# main_board_v2_3.net
KiCad netlist of a schematic drawn in EAGLE
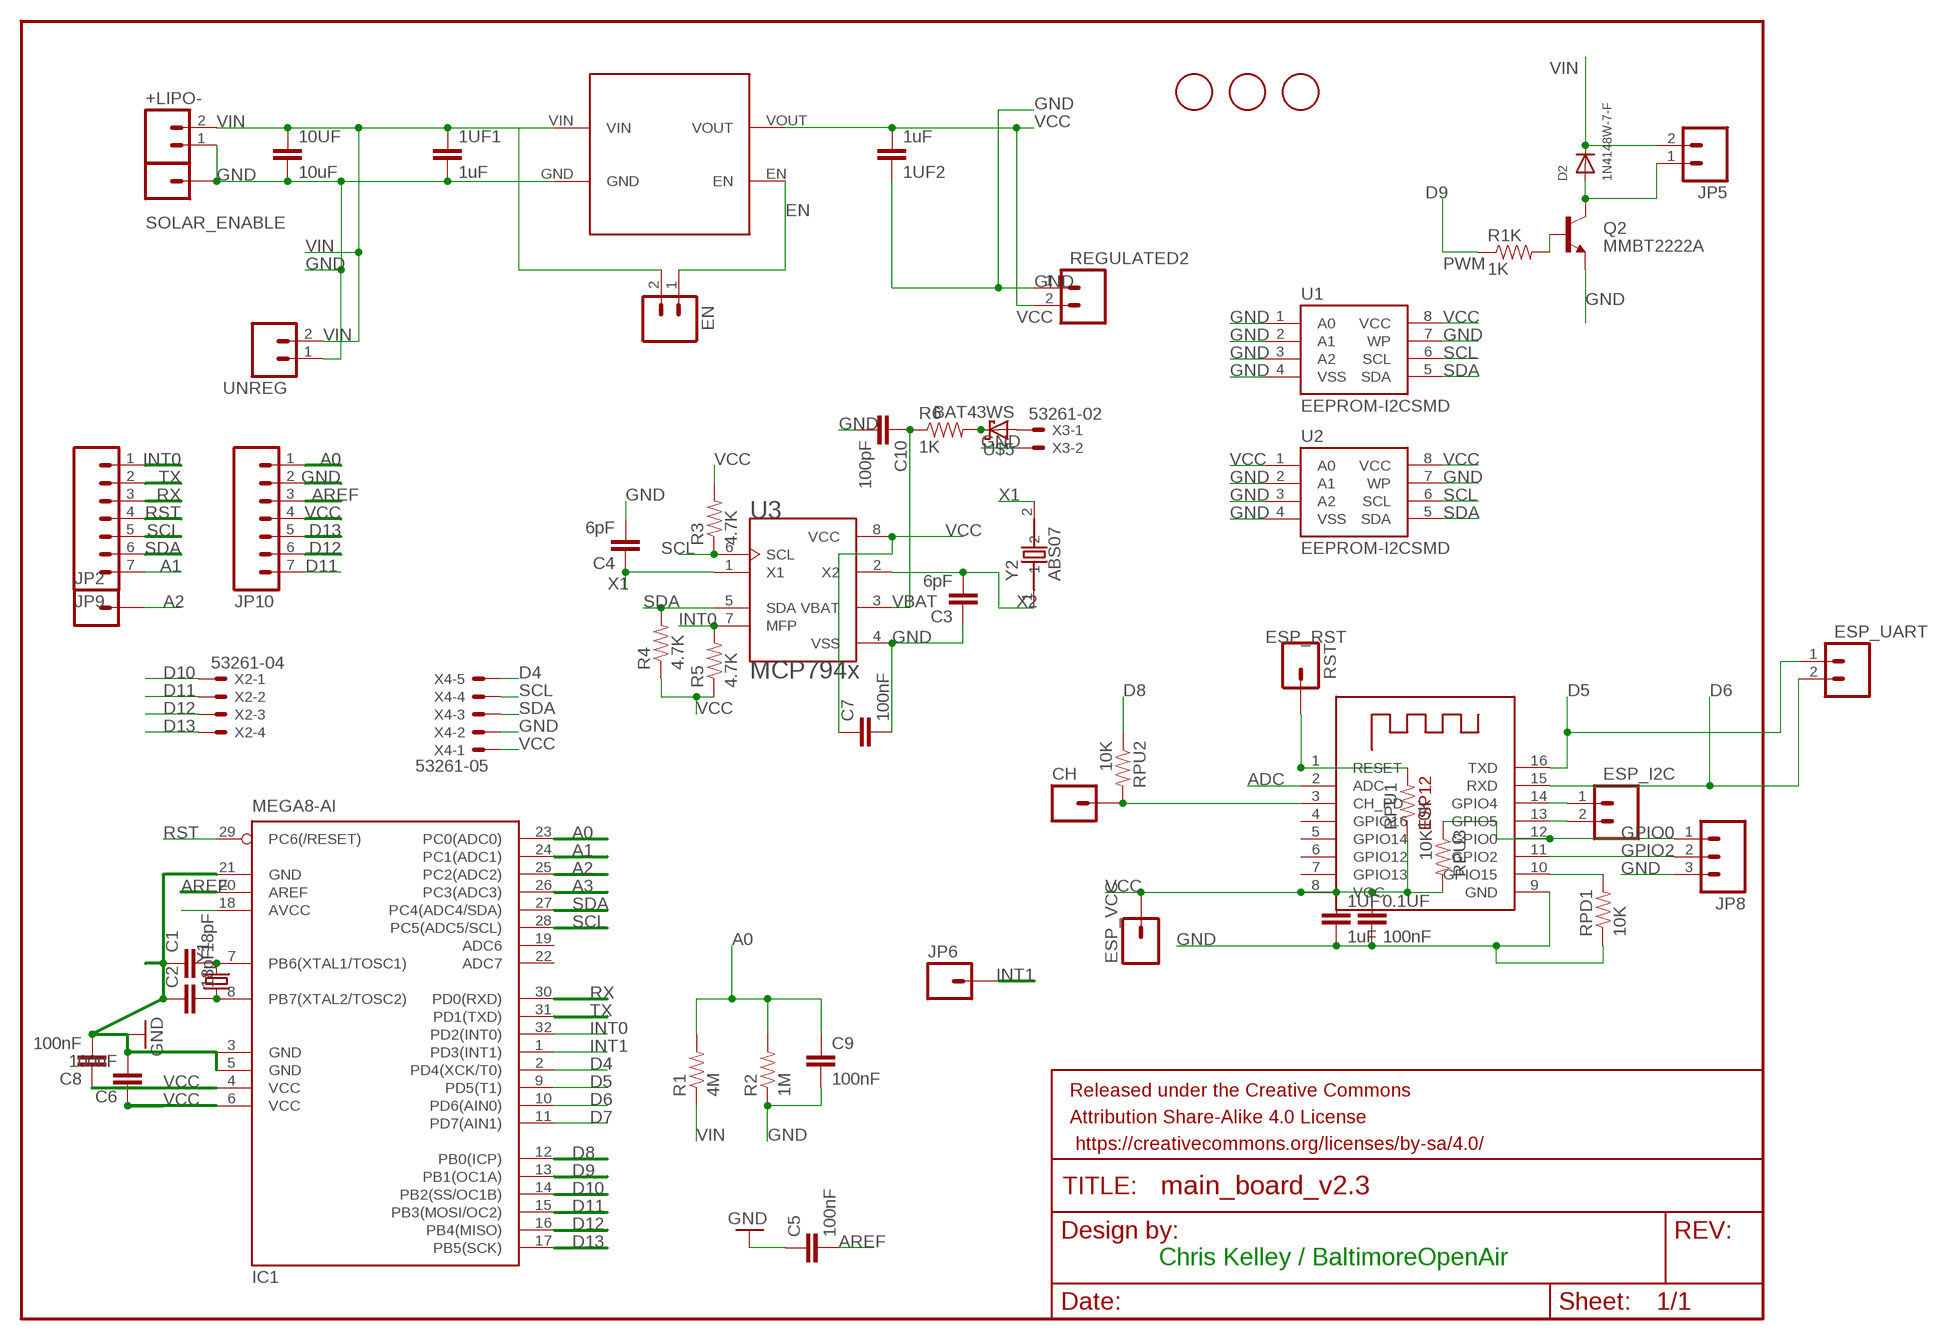
[diagram p0: schematic, sheet 1]

(export (version "E")
  (design (tool "Eeschema 10.0.6"))
  (components
    (comp (ref "+LIPO-")
      (value "M02PTH")
      (footprint "eagle-import:1X02")
      (libsource (lib "eagle-import") (part "M02PTH"))
    )
    (comp (ref "0.1UF")
      (value "100nF")
      (footprint "eagle-import:0603-CAP")
      (libsource (lib "eagle-import") (part "SparkFun-Passives_CAP0603-CAP"))
    )
    (comp (ref "1UF")
      (value "1uF")
      (footprint "eagle-import:0603-CAP")
      (libsource (lib "eagle-import") (part "SparkFun-Passives_CAP0603-CAP"))
    )
    (comp (ref "1UF1")
      (value "1uF")
      (footprint "eagle-import:0603-CAP")
      (libsource (lib "eagle-import") (part "SparkFun-Passives_CAP0603-CAP"))
    )
    (comp (ref "1UF2")
      (value "1uF")
      (footprint "eagle-import:0603-CAP")
      (libsource (lib "eagle-import") (part "SparkFun-Passives_CAP0603-CAP"))
    )
    (comp (ref "10UF")
      (value "10uF")
      (footprint "eagle-import:0805")
      (libsource (lib "eagle-import") (part "SparkFun-Passives_CAP0805"))
    )
    (comp (ref "C1")
      (value "18pF")
      (footprint "eagle-import:0603-CAP")
      (libsource (lib "eagle-import") (part "CAP0603-CAP"))
    )
    (comp (ref "C2")
      (value "18pF")
      (footprint "eagle-import:0603-CAP")
      (libsource (lib "eagle-import") (part "CAP0603-CAP"))
    )
    (comp (ref "C3")
      (value "6pF")
      (footprint "eagle-import:0603-CAP")
      (libsource (lib "eagle-import") (part "SparkFun-Passives_CAP0603-CAP"))
    )
    (comp (ref "C4")
      (value "6pF")
      (footprint "eagle-import:0603-CAP")
      (libsource (lib "eagle-import") (part "SparkFun-Passives_CAP0603-CAP"))
    )
    (comp (ref "C5")
      (value "100nF")
      (footprint "eagle-import:0603-CAP")
      (libsource (lib "eagle-import") (part "CAP0603-CAP"))
    )
    (comp (ref "C6")
      (value "100nF")
      (footprint "eagle-import:0603-CAP")
      (libsource (lib "eagle-import") (part "CAP0603-CAP"))
    )
    (comp (ref "C7")
      (value "100nF")
      (footprint "eagle-import:0603-CAP")
      (libsource (lib "eagle-import") (part "SparkFun-Passives_CAP0603-CAP"))
    )
    (comp (ref "C8")
      (value "100nF")
      (footprint "eagle-import:0603-CAP")
      (libsource (lib "eagle-import") (part "CAP0603-CAP"))
    )
    (comp (ref "C9")
      (value "100nF")
      (footprint "eagle-import:0603-CAP")
      (libsource (lib "eagle-import") (part "SparkFun-Passives_CAP0603-CAP"))
    )
    (comp (ref "C10")
      (value "100pF")
      (footprint "eagle-import:0603-CAP")
      (libsource (lib "eagle-import") (part "SparkFun-Passives_CAP0603-CAP"))
    )
    (comp (ref "CH")
      (value "M01PTH")
      (footprint "eagle-import:1X01")
      (libsource (lib "eagle-import") (part "M01PTH"))
    )
    (comp (ref "D2")
      (value "1N4148W-7-F")
      (footprint "eagle-import:SOD-123")
      (libsource (lib "eagle-import") (part "DIODESOD-123"))
    )
    (comp (ref "EN")
      (value "M02PTH")
      (footprint "eagle-import:1X02")
      (libsource (lib "eagle-import") (part "M02PTH"))
    )
    (comp (ref "ESP_I2C")
      (value "M02PTH")
      (footprint "eagle-import:1X02")
      (libsource (lib "eagle-import") (part "M02PTH"))
    )
    (comp (ref "ESP_UART")
      (value "M02PTH")
      (footprint "eagle-import:1X02")
      (libsource (lib "eagle-import") (part "M02PTH"))
    )
    (comp (ref "ESP_VCC")
      (value "M01PTH")
      (footprint "eagle-import:1X01")
      (libsource (lib "eagle-import") (part "M01PTH"))
    )
    (comp (ref "FRAME1")
      (value "FRAME-LETTER")
      (footprint "eagle-import:CREATIVE_COMMONS")
      (libsource (lib "eagle-import") (part "FRAME-LETTER"))
    )
    (comp (ref "IC1")
      (value "MEGA8-AI")
      (footprint "eagle-import:TQFP32-08")
      (fields (field (name "MPN") "ATMEGA8-16AU"))
      (libsource (lib "eagle-import") (part "MEGA8-AI"))
    )
    (comp (ref "JP2")
      (value "M01PTH")
      (footprint "eagle-import:1X01")
      (libsource (lib "eagle-import") (part "M01PTH"))
    )
    (comp (ref "JP5")
      (value "M02-JST-2MM-SMT")
      (footprint "eagle-import:JST-2-SMD")
      (libsource (lib "eagle-import") (part "M02-JST-2MM-SMT"))
    )
    (comp (ref "JP6")
      (value "M01PTH")
      (footprint "eagle-import:1X01")
      (libsource (lib "eagle-import") (part "M01PTH"))
    )
    (comp (ref "JP8")
      (value "M03PTH")
      (footprint "eagle-import:1X03")
      (libsource (lib "eagle-import") (part "M03PTH"))
    )
    (comp (ref "JP9")
      (value "M07")
      (footprint "eagle-import:1X07")
      (libsource (lib "eagle-import") (part "M07"))
    )
    (comp (ref "JP10")
      (value "M07")
      (footprint "eagle-import:1X07")
      (libsource (lib "eagle-import") (part "M07"))
    )
    (comp (ref "Q2")
      (value "MMBT2222A")
      (footprint "eagle-import:SOT23-3")
      (libsource (lib "eagle-import") (part "TRANSISTOR_NPNMMBT2222A"))
    )
    (comp (ref "R1")
      (value "4M")
      (footprint "eagle-import:0603-RES")
      (libsource (lib "eagle-import") (part "RESISTOR0603"))
    )
    (comp (ref "R1K")
      (value "1K")
      (footprint "eagle-import:0603-RES")
      (libsource (lib "eagle-import") (part "RESISTOR0603-RES"))
    )
    (comp (ref "R2")
      (value "1M")
      (footprint "eagle-import:0603-RES")
      (libsource (lib "eagle-import") (part "RESISTOR0603"))
    )
    (comp (ref "R3")
      (value "4.7K")
      (footprint "eagle-import:0603-RES")
      (libsource (lib "eagle-import") (part "RESISTOR0603-RES"))
    )
    (comp (ref "R4")
      (value "4.7K")
      (footprint "eagle-import:0603-RES")
      (libsource (lib "eagle-import") (part "RESISTOR0603-RES"))
    )
    (comp (ref "R5")
      (value "4.7K")
      (footprint "eagle-import:0603-RES")
      (libsource (lib "eagle-import") (part "RESISTOR0603-RES"))
    )
    (comp (ref "R6")
      (value "1K")
      (footprint "eagle-import:0603-RES")
      (libsource (lib "eagle-import") (part "RESISTOR0603-RES"))
    )
    (comp (ref "REGULATED2")
      (value "M02PTH")
      (footprint "eagle-import:1X02")
      (libsource (lib "eagle-import") (part "M02PTH"))
    )
    (comp (ref "RPD1")
      (value "10K")
      (footprint "eagle-import:0603-RES")
      (libsource (lib "eagle-import") (part "RESISTOR0603-RES"))
    )
    (comp (ref "RPU1")
      (value "10K")
      (footprint "eagle-import:0603-RES")
      (libsource (lib "eagle-import") (part "RESISTOR0603-RES"))
    )
    (comp (ref "RPU2")
      (value "10K")
      (footprint "eagle-import:0603-RES")
      (libsource (lib "eagle-import") (part "RESISTOR0603-RES"))
    )
    (comp (ref "RPU3")
      (value "10K")
      (footprint "eagle-import:0603-RES")
      (libsource (lib "eagle-import") (part "RESISTOR0603-RES"))
    )
    (comp (ref "RST")
      (value "M01PTH")
      (footprint "eagle-import:1X01")
      (libsource (lib "eagle-import") (part "M01PTH"))
    )
    (comp (ref "SOLAR_ENABLE")
      (value "M01PTH")
      (footprint "eagle-import:1X01")
      (libsource (lib "eagle-import") (part "M01PTH"))
    )
    (comp (ref "U$3")
      (value "FIDUCIAL")
      (footprint "eagle-import:FIDUCIAL_1MM")
      (libsource (lib "eagle-import") (part "FIDUCIAL"))
    )
    (comp (ref "U$4")
      (value "AP2112K")
      (footprint "eagle-import:AP2112K-SOT23-5")
      (libsource (lib "eagle-import") (part "AP2112K"))
    )
    (comp (ref "U$5")
      (value "BAT43WS")
      (footprint "eagle-import:BAT43WS")
      (libsource (lib "eagle-import") (part "BAT43WS"))
    )
    (comp (ref "U$6")
      (value "FIDUCIAL")
      (footprint "eagle-import:FIDUCIAL_1MM")
      (libsource (lib "eagle-import") (part "FIDUCIAL"))
    )
    (comp (ref "U$7")
      (value "FIDUCIAL")
      (footprint "eagle-import:FIDUCIAL_1MM")
      (libsource (lib "eagle-import") (part "FIDUCIAL"))
    )
    (comp (ref "U1")
      (value "EEPROM-I2CSMD")
      (footprint "eagle-import:SO08")
      (libsource (lib "eagle-import") (part "EEPROM-I2CSMD"))
    )
    (comp (ref "U2")
      (value "EEPROM-I2CSMD")
      (footprint "eagle-import:SO08")
      (libsource (lib "eagle-import") (part "EEPROM-I2CSMD"))
    )
    (comp (ref "U3")
      (value "MCP794x")
      (footprint "eagle-import:SOIC127P600X175-8N")
      (fields (field (name "MF") "Microchip") (field (name "MP") "MCP7940M-I/SN"))
      (libsource (lib "eagle-import") (part "MCP7940M-I/SN"))
    )
    (comp (ref "UNREG")
      (value "M02PTH")
      (footprint "eagle-import:1X02")
      (libsource (lib "eagle-import") (part "M02PTH"))
    )
    (comp (ref "X1")
      (value "ESP-12")
      (footprint "eagle-import:ESP-12")
      (libsource (lib "eagle-import") (part "ESP-12"))
    )
    (comp (ref "X2")
      (value "53261-04")
      (footprint "eagle-import:53261-04")
      (libsource (lib "eagle-import") (part "53?-04261"))
    )
    (comp (ref "X3")
      (value "53261-02")
      (footprint "eagle-import:53261-02")
      (libsource (lib "eagle-import") (part "53?-02261"))
    )
    (comp (ref "X4")
      (value "53261-05")
      (footprint "eagle-import:53261-05")
      (libsource (lib "eagle-import") (part "53?-05261"))
    )
    (comp (ref "Y1")
      (value "CRYSTAL5X3")
      (footprint "eagle-import:CRYSTAL-SMD-5X3")
      (libsource (lib "eagle-import") (part "CRYSTAL5X3"))
    )
    (comp (ref "Y2")
      (value "ABS07")
      (footprint "eagle-import:XTAL320X150X90")
      (fields (field (name "MF") "Abracon") (field (name "MP") "ABS07-32.768KHZ-T"))
      (libsource (lib "eagle-import") (part "ABS07-32.768KHZ-T"))
    )
  )
  (nets
    (net (code "1") (name "/A0") (class "Default")
      (node (ref "C9") (pin "1") (pinfunction "1_1") (pintype "passive"))
      (node (ref "IC1") (pin "23") (pinfunction "PC0(ADC0)_23") (pintype "bidirectional"))
      (node (ref "JP10") (pin "1") (pinfunction "1_1") (pintype "passive"))
      (node (ref "R1") (pin "2") (pinfunction "2_2") (pintype "passive"))
      (node (ref "R2") (pin "2") (pinfunction "2_2") (pintype "passive"))
    )
    (net (code "2") (name "/A1") (class "Default")
      (node (ref "IC1") (pin "24") (pinfunction "PC1(ADC1)_24") (pintype "bidirectional"))
      (node (ref "JP9") (pin "7") (pinfunction "7_7") (pintype "passive"))
    )
    (net (code "3") (name "/A2") (class "Default")
      (node (ref "IC1") (pin "25") (pinfunction "PC2(ADC2)_25") (pintype "bidirectional"))
      (node (ref "JP2") (pin "1") (pinfunction "1_1") (pintype "passive"))
    )
    (net (code "4") (name "/A3") (class "Default")
      (node (ref "IC1") (pin "26") (pinfunction "PC3(ADC3)_26") (pintype "bidirectional"))
    )
    (net (code "5") (name "/ADC") (class "Default")
      (node (ref "X1") (pin "2") (pinfunction "ADC_2") (pintype "passive"))
    )
    (net (code "6") (name "/AREF") (class "Default")
      (node (ref "C5") (pin "2") (pinfunction "2_2") (pintype "passive"))
      (node (ref "IC1") (pin "20") (pinfunction "AREF_20") (pintype "passive"))
      (node (ref "JP10") (pin "3") (pinfunction "3_3") (pintype "passive"))
    )
    (net (code "7") (name "/D4") (class "Default")
      (node (ref "IC1") (pin "2") (pinfunction "PD4(XCK/T0)_2") (pintype "bidirectional"))
      (node (ref "X4") (pin "5") (pinfunction "S_5") (pintype "passive"))
    )
    (net (code "8") (name "/D5") (class "Default")
      (node (ref "ESP_UART") (pin "1") (pinfunction "1_1") (pintype "passive"))
      (node (ref "IC1") (pin "9") (pinfunction "PD5(T1)_9") (pintype "bidirectional"))
      (node (ref "X1") (pin "16") (pinfunction "TXD_16") (pintype "output"))
    )
    (net (code "9") (name "/D6") (class "Default")
      (node (ref "ESP_UART") (pin "2") (pinfunction "2_2") (pintype "passive"))
      (node (ref "IC1") (pin "10") (pinfunction "PD6(AIN0)_10") (pintype "bidirectional"))
      (node (ref "X1") (pin "15") (pinfunction "RXD_15") (pintype "input"))
    )
    (net (code "10") (name "/D7") (class "Default")
      (node (ref "IC1") (pin "11") (pinfunction "PD7(AIN1)_11") (pintype "bidirectional"))
    )
    (net (code "11") (name "/D8") (class "Default")
      (node (ref "IC1") (pin "12") (pinfunction "PB0(ICP)_12") (pintype "bidirectional"))
      (node (ref "RPU2") (pin "1") (pinfunction "1_1") (pintype "passive"))
    )
    (net (code "12") (name "/D9") (class "Default")
      (node (ref "IC1") (pin "13") (pinfunction "PB1(OC1A)_13") (pintype "bidirectional"))
      (node (ref "R1K") (pin "1") (pinfunction "1_1") (pintype "passive"))
    )
    (net (code "13") (name "/D10") (class "Default")
      (node (ref "IC1") (pin "14") (pinfunction "PB2(SS/OC1B)_14") (pintype "bidirectional"))
      (node (ref "X2") (pin "1") (pinfunction "S_1") (pintype "passive"))
    )
    (net (code "14") (name "/D11") (class "Default")
      (node (ref "IC1") (pin "15") (pinfunction "PB3(MOSI/OC2)_15") (pintype "bidirectional"))
      (node (ref "JP10") (pin "7") (pinfunction "7_7") (pintype "passive"))
      (node (ref "X2") (pin "2") (pinfunction "S_2") (pintype "passive"))
    )
    (net (code "15") (name "/D12") (class "Default")
      (node (ref "IC1") (pin "16") (pinfunction "PB4(MISO)_16") (pintype "bidirectional"))
      (node (ref "JP10") (pin "6") (pinfunction "6_6") (pintype "passive"))
      (node (ref "X2") (pin "3") (pinfunction "S_3") (pintype "passive"))
    )
    (net (code "16") (name "/D13") (class "Default")
      (node (ref "IC1") (pin "17") (pinfunction "PB5(SCK)_17") (pintype "bidirectional"))
      (node (ref "JP10") (pin "5") (pinfunction "5_5") (pintype "passive"))
      (node (ref "X2") (pin "4") (pinfunction "S_4") (pintype "passive"))
    )
    (net (code "17") (name "/EN") (class "Default")
      (node (ref "EN") (pin "1") (pinfunction "1_1") (pintype "passive"))
      (node (ref "U$4") (pin "EN") (pinfunction "EN_EN") (pintype "bidirectional"))
    )
    (net (code "18") (name "/ESP_RST") (class "Default")
      (node (ref "RPU1") (pin "2") (pinfunction "2_2") (pintype "passive"))
      (node (ref "RST") (pin "1") (pinfunction "1_1") (pintype "passive"))
      (node (ref "X1") (pin "1") (pinfunction "RESET_1") (pintype "input"))
    )
    (net (code "19") (name "/GPIO0") (class "Default")
      (node (ref "JP8") (pin "1") (pinfunction "1_1") (pintype "passive"))
      (node (ref "RPU3") (pin "1") (pinfunction "1_1") (pintype "passive"))
      (node (ref "X1") (pin "12") (pinfunction "GPIO0_12") (pintype "bidirectional"))
    )
    (net (code "20") (name "/GPIO2") (class "Default")
      (node (ref "JP8") (pin "2") (pinfunction "2_2") (pintype "passive"))
      (node (ref "X1") (pin "11") (pinfunction "GPIO2_11") (pintype "bidirectional"))
    )
    (net (code "21") (name "/INT0") (class "Default")
      (node (ref "IC1") (pin "32") (pinfunction "PD2(INT0)_32") (pintype "bidirectional"))
      (node (ref "JP9") (pin "1") (pinfunction "1_1") (pintype "passive"))
      (node (ref "R5") (pin "2") (pinfunction "2_2") (pintype "passive"))
      (node (ref "U3") (pin "7") (pinfunction "MFP_7") (pintype "bidirectional"))
    )
    (net (code "22") (name "/INT1") (class "Default")
      (node (ref "IC1") (pin "1") (pinfunction "PD3(INT1)_1") (pintype "bidirectional"))
      (node (ref "JP6") (pin "1") (pinfunction "1_1") (pintype "passive"))
    )
    (net (code "23") (name "/PWM") (class "Default")
      (node (ref "Q2") (pin "1") (pinfunction "B_1") (pintype "passive"))
      (node (ref "R1K") (pin "2") (pinfunction "2_2") (pintype "passive"))
    )
    (net (code "24") (name "/RST") (class "Default")
      (node (ref "IC1") (pin "29") (pinfunction "PC6(/RESET)_29") (pintype "bidirectional"))
      (node (ref "JP9") (pin "4") (pinfunction "4_4") (pintype "passive"))
    )
    (net (code "25") (name "/RX") (class "Default")
      (node (ref "IC1") (pin "30") (pinfunction "PD0(RXD)_30") (pintype "bidirectional"))
      (node (ref "JP9") (pin "3") (pinfunction "3_3") (pintype "passive"))
    )
    (net (code "26") (name "/SCL") (class "Default")
      (node (ref "IC1") (pin "28") (pinfunction "PC5(ADC5/SCL)_28") (pintype "bidirectional"))
      (node (ref "JP9") (pin "5") (pinfunction "5_5") (pintype "passive"))
      (node (ref "R3") (pin "1") (pinfunction "1_1") (pintype "passive"))
      (node (ref "U1") (pin "6") (pinfunction "SCL_6") (pintype "bidirectional"))
      (node (ref "U2") (pin "6") (pinfunction "SCL_6") (pintype "bidirectional"))
      (node (ref "U3") (pin "6") (pinfunction "SCL_6") (pintype "input"))
      (node (ref "X4") (pin "4") (pinfunction "S_4") (pintype "passive"))
    )
    (net (code "27") (name "/SDA") (class "Default")
      (node (ref "IC1") (pin "27") (pinfunction "PC4(ADC4/SDA)_27") (pintype "bidirectional"))
      (node (ref "JP9") (pin "6") (pinfunction "6_6") (pintype "passive"))
      (node (ref "R4") (pin "2") (pinfunction "2_2") (pintype "passive"))
      (node (ref "U1") (pin "5") (pinfunction "SDA_5") (pintype "bidirectional"))
      (node (ref "U2") (pin "5") (pinfunction "SDA_5") (pintype "bidirectional"))
      (node (ref "U3") (pin "5") (pinfunction "SDA_5") (pintype "bidirectional"))
      (node (ref "X4") (pin "3") (pinfunction "S_3") (pintype "passive"))
    )
    (net (code "28") (name "/TX") (class "Default")
      (node (ref "IC1") (pin "31") (pinfunction "PD1(TXD)_31") (pintype "bidirectional"))
      (node (ref "JP9") (pin "2") (pinfunction "2_2") (pintype "passive"))
    )
    (net (code "29") (name "/VBAT") (class "Default")
      (node (ref "C10") (pin "1") (pinfunction "1_1") (pintype "passive"))
      (node (ref "R6") (pin "1") (pinfunction "1_1") (pintype "passive"))
      (node (ref "U3") (pin "3") (pinfunction "VBAT_3") (pintype "power_in"))
    )
    (net (code "30") (name "/VCC") (class "Default")
      (node (ref "0.1UF") (pin "1") (pinfunction "1_1") (pintype "passive"))
      (node (ref "1UF") (pin "1") (pinfunction "1_1") (pintype "passive"))
      (node (ref "1UF2") (pin "2") (pinfunction "2_2") (pintype "passive"))
      (node (ref "C6") (pin "1") (pinfunction "1_1") (pintype "passive"))
      (node (ref "C7") (pin "1") (pinfunction "1_1") (pintype "passive"))
      (node (ref "C8") (pin "1") (pinfunction "1_1") (pintype "passive"))
      (node (ref "ESP_VCC") (pin "1") (pinfunction "1_1") (pintype "passive"))
      (node (ref "IC1") (pin "18") (pinfunction "AVCC_18") (pintype "power_in"))
      (node (ref "IC1") (pin "4") (pinfunction "VCC_4") (pintype "power_in"))
      (node (ref "IC1") (pin "6") (pinfunction "VCC_6") (pintype "power_in"))
      (node (ref "JP10") (pin "4") (pinfunction "4_4") (pintype "passive"))
      (node (ref "R3") (pin "2") (pinfunction "2_2") (pintype "passive"))
      (node (ref "R4") (pin "1") (pinfunction "1_1") (pintype "passive"))
      (node (ref "R5") (pin "1") (pinfunction "1_1") (pintype "passive"))
      (node (ref "REGULATED2") (pin "2") (pinfunction "2_2") (pintype "passive"))
      (node (ref "RPU1") (pin "1") (pinfunction "1_1") (pintype "passive"))
      (node (ref "RPU3") (pin "2") (pinfunction "2_2") (pintype "passive"))
      (node (ref "U$4") (pin "VOUT") (pinfunction "VOUT_VOUT") (pintype "bidirectional"))
      (node (ref "U1") (pin "8") (pinfunction "VCC_8") (pintype "power_in"))
      (node (ref "U2") (pin "1") (pinfunction "A0_1") (pintype "bidirectional"))
      (node (ref "U2") (pin "8") (pinfunction "VCC_8") (pintype "power_in"))
      (node (ref "U3") (pin "8") (pinfunction "VCC_8") (pintype "power_in"))
      (node (ref "X1") (pin "8") (pinfunction "VCC_8") (pintype "power_in"))
      (node (ref "X4") (pin "1") (pinfunction "S_1") (pintype "passive"))
    )
    (net (code "31") (name "/VIN") (class "Default")
      (node (ref "+LIPO-") (pin "2") (pinfunction "2_2") (pintype "passive"))
      (node (ref "10UF") (pin "1") (pinfunction "1_1") (pintype "passive"))
      (node (ref "1UF1") (pin "1") (pinfunction "1_1") (pintype "passive"))
      (node (ref "D2") (pin "C") (pinfunction "C_C") (pintype "passive"))
      (node (ref "EN") (pin "2") (pinfunction "2_2") (pintype "passive"))
      (node (ref "JP5") (pin "2") (pinfunction "1_2") (pintype "passive"))
      (node (ref "R1") (pin "1") (pinfunction "1_1") (pintype "passive"))
      (node (ref "U$4") (pin "VIN") (pinfunction "VIN_VIN") (pintype "bidirectional"))
      (node (ref "UNREG") (pin "2") (pinfunction "2_2") (pintype "passive"))
    )
    (net (code "32") (name "/X1") (class "Default")
      (node (ref "C4") (pin "1") (pinfunction "1_1") (pintype "passive"))
      (node (ref "U3") (pin "1") (pinfunction "X1_1") (pintype "input"))
      (node (ref "Y2") (pin "2") (pinfunction "2_2") (pintype "passive"))
    )
    (net (code "33") (name "/X2") (class "Default")
      (node (ref "C3") (pin "2") (pinfunction "2_2") (pintype "passive"))
      (node (ref "U3") (pin "2") (pinfunction "X2_2") (pintype "output"))
      (node (ref "Y2") (pin "1") (pinfunction "1_1") (pintype "passive"))
    )
    (net (code "34") (name "GND") (class "Default")
      (node (ref "+LIPO-") (pin "1") (pinfunction "1_1") (pintype "passive"))
      (node (ref "0.1UF") (pin "2") (pinfunction "2_2") (pintype "passive"))
      (node (ref "10UF") (pin "2") (pinfunction "2_2") (pintype "passive"))
      (node (ref "1UF") (pin "2") (pinfunction "2_2") (pintype "passive"))
      (node (ref "1UF1") (pin "2") (pinfunction "2_2") (pintype "passive"))
      (node (ref "1UF2") (pin "1") (pinfunction "1_1") (pintype "passive"))
      (node (ref "C1") (pin "1") (pinfunction "1_1") (pintype "passive"))
      (node (ref "C10") (pin "2") (pinfunction "2_2") (pintype "passive"))
      (node (ref "C2") (pin "1") (pinfunction "1_1") (pintype "passive"))
      (node (ref "C3") (pin "1") (pinfunction "1_1") (pintype "passive"))
      (node (ref "C4") (pin "2") (pinfunction "2_2") (pintype "passive"))
      (node (ref "C5") (pin "1") (pinfunction "1_1") (pintype "passive"))
      (node (ref "C6") (pin "2") (pinfunction "2_2") (pintype "passive"))
      (node (ref "C7") (pin "2") (pinfunction "2_2") (pintype "passive"))
      (node (ref "C8") (pin "2") (pinfunction "2_2") (pintype "passive"))
      (node (ref "C9") (pin "2") (pinfunction "2_2") (pintype "passive"))
      (node (ref "IC1") (pin "21") (pinfunction "GND_21") (pintype "power_in"))
      (node (ref "IC1") (pin "3") (pinfunction "GND_3") (pintype "power_in"))
      (node (ref "IC1") (pin "5") (pinfunction "GND_5") (pintype "power_in"))
      (node (ref "JP10") (pin "2") (pinfunction "2_2") (pintype "passive"))
      (node (ref "JP8") (pin "3") (pinfunction "3_3") (pintype "passive"))
      (node (ref "Q2") (pin "2") (pinfunction "E_2") (pintype "passive"))
      (node (ref "R2") (pin "1") (pinfunction "1_1") (pintype "passive"))
      (node (ref "REGULATED2") (pin "1") (pinfunction "1_1") (pintype "passive"))
      (node (ref "RPD1") (pin "1") (pinfunction "1_1") (pintype "passive"))
      (node (ref "SOLAR_ENABLE") (pin "1") (pinfunction "1_1") (pintype "passive"))
      (node (ref "U$4") (pin "GND") (pinfunction "GND_GND") (pintype "bidirectional"))
      (node (ref "U1") (pin "1") (pinfunction "A0_1") (pintype "bidirectional"))
      (node (ref "U1") (pin "2") (pinfunction "A1_2") (pintype "bidirectional"))
      (node (ref "U1") (pin "3") (pinfunction "A2_3") (pintype "bidirectional"))
      (node (ref "U1") (pin "4") (pinfunction "VSS_4") (pintype "power_in"))
      (node (ref "U1") (pin "7") (pinfunction "WP_7") (pintype "bidirectional"))
      (node (ref "U2") (pin "2") (pinfunction "A1_2") (pintype "bidirectional"))
      (node (ref "U2") (pin "3") (pinfunction "A2_3") (pintype "bidirectional"))
      (node (ref "U2") (pin "4") (pinfunction "VSS_4") (pintype "power_in"))
      (node (ref "U2") (pin "7") (pinfunction "WP_7") (pintype "bidirectional"))
      (node (ref "U3") (pin "4") (pinfunction "VSS_4") (pintype "passive"))
      (node (ref "UNREG") (pin "1") (pinfunction "1_1") (pintype "passive"))
      (node (ref "X1") (pin "9") (pinfunction "GND_9") (pintype "power_in"))
      (node (ref "X3") (pin "2") (pinfunction "S_2") (pintype "passive"))
      (node (ref "X4") (pin "2") (pinfunction "S_2") (pintype "passive"))
    )
    (net (code "35") (name "Net-(IC1-PB6(XTAL1{slash}TOSC1))") (class "Default")
      (node (ref "C1") (pin "2") (pinfunction "2_2") (pintype "passive"))
      (node (ref "IC1") (pin "7") (pinfunction "PB6(XTAL1/TOSC1)_7") (pintype "bidirectional"))
      (node (ref "Y1") (pin "3") (pinfunction "2_3") (pintype "passive"))
    )
    (net (code "36") (name "Net-(IC1-PB7(XTAL2{slash}TOSC2))") (class "Default")
      (node (ref "C2") (pin "2") (pinfunction "2_2") (pintype "passive"))
      (node (ref "IC1") (pin "8") (pinfunction "PB7(XTAL2/TOSC2)_8") (pintype "bidirectional"))
      (node (ref "Y1") (pin "1") (pinfunction "1_1") (pintype "passive"))
    )
    (net (code "37") (name "Net-(JP5-2)") (class "Default")
      (node (ref "D2") (pin "A") (pinfunction "A_A") (pintype "passive"))
      (node (ref "JP5") (pin "1") (pinfunction "2_1") (pintype "passive"))
      (node (ref "Q2") (pin "3") (pinfunction "C_3") (pintype "passive"))
    )
    (net (code "38") (name "Net-(U$5-A)") (class "Default")
      (node (ref "R6") (pin "2") (pinfunction "2_2") (pintype "passive"))
      (node (ref "U$5") (pin "PIN2") (pinfunction "A_PIN2") (pintype "passive"))
    )
    (net (code "39") (name "Net-(U$5-C)") (class "Default")
      (node (ref "U$5") (pin "PIN1") (pinfunction "C_PIN1") (pintype "passive"))
      (node (ref "X3") (pin "1") (pinfunction "S_1") (pintype "passive"))
    )
    (net (code "40") (name "Net-(X1-CH_PD)") (class "Default")
      (node (ref "CH") (pin "1") (pinfunction "1_1") (pintype "passive"))
      (node (ref "RPU2") (pin "2") (pinfunction "2_2") (pintype "passive"))
      (node (ref "X1") (pin "3") (pinfunction "CH_PD_3") (pintype "input"))
    )
    (net (code "41") (name "Net-(X1-GPIO4)") (class "Default")
      (node (ref "ESP_I2C") (pin "1") (pinfunction "1_1") (pintype "passive"))
      (node (ref "X1") (pin "14") (pinfunction "GPIO4_14") (pintype "bidirectional"))
    )
    (net (code "42") (name "Net-(X1-GPIO5)") (class "Default")
      (node (ref "ESP_I2C") (pin "2") (pinfunction "2_2") (pintype "passive"))
      (node (ref "X1") (pin "13") (pinfunction "GPIO5_13") (pintype "bidirectional"))
    )
    (net (code "43") (name "Net-(X1-GPIO15)") (class "Default")
      (node (ref "RPD1") (pin "2") (pinfunction "2_2") (pintype "passive"))
      (node (ref "X1") (pin "10") (pinfunction "GPIO15_10") (pintype "bidirectional"))
    )
    (net (code "44") (name "unconnected-(IC1-ADC6-Pad19)") (class "Default")
      (node (ref "IC1") (pin "19") (pinfunction "ADC6_19") (pintype "bidirectional"))
    )
    (net (code "45") (name "unconnected-(IC1-ADC7-Pad22)") (class "Default")
      (node (ref "IC1") (pin "22") (pinfunction "ADC7_22") (pintype "bidirectional"))
    )
    (net (code "46") (name "unconnected-(X1-GPIO12-Pad6)") (class "Default")
      (node (ref "X1") (pin "6") (pinfunction "GPIO12_6") (pintype "bidirectional"))
    )
    (net (code "47") (name "unconnected-(X1-GPIO13-Pad7)") (class "Default")
      (node (ref "X1") (pin "7") (pinfunction "GPIO13_7") (pintype "bidirectional"))
    )
    (net (code "48") (name "unconnected-(X1-GPIO14-Pad5)") (class "Default")
      (node (ref "X1") (pin "5") (pinfunction "GPIO14_5") (pintype "bidirectional"))
    )
    (net (code "49") (name "unconnected-(X1-GPIO16-Pad4)") (class "Default")
      (node (ref "X1") (pin "4") (pinfunction "GPIO16_4") (pintype "bidirectional"))
    )
  )
)
